# Analog_Section.net
KiCad netlist of a schematic drawn in Altium Designer
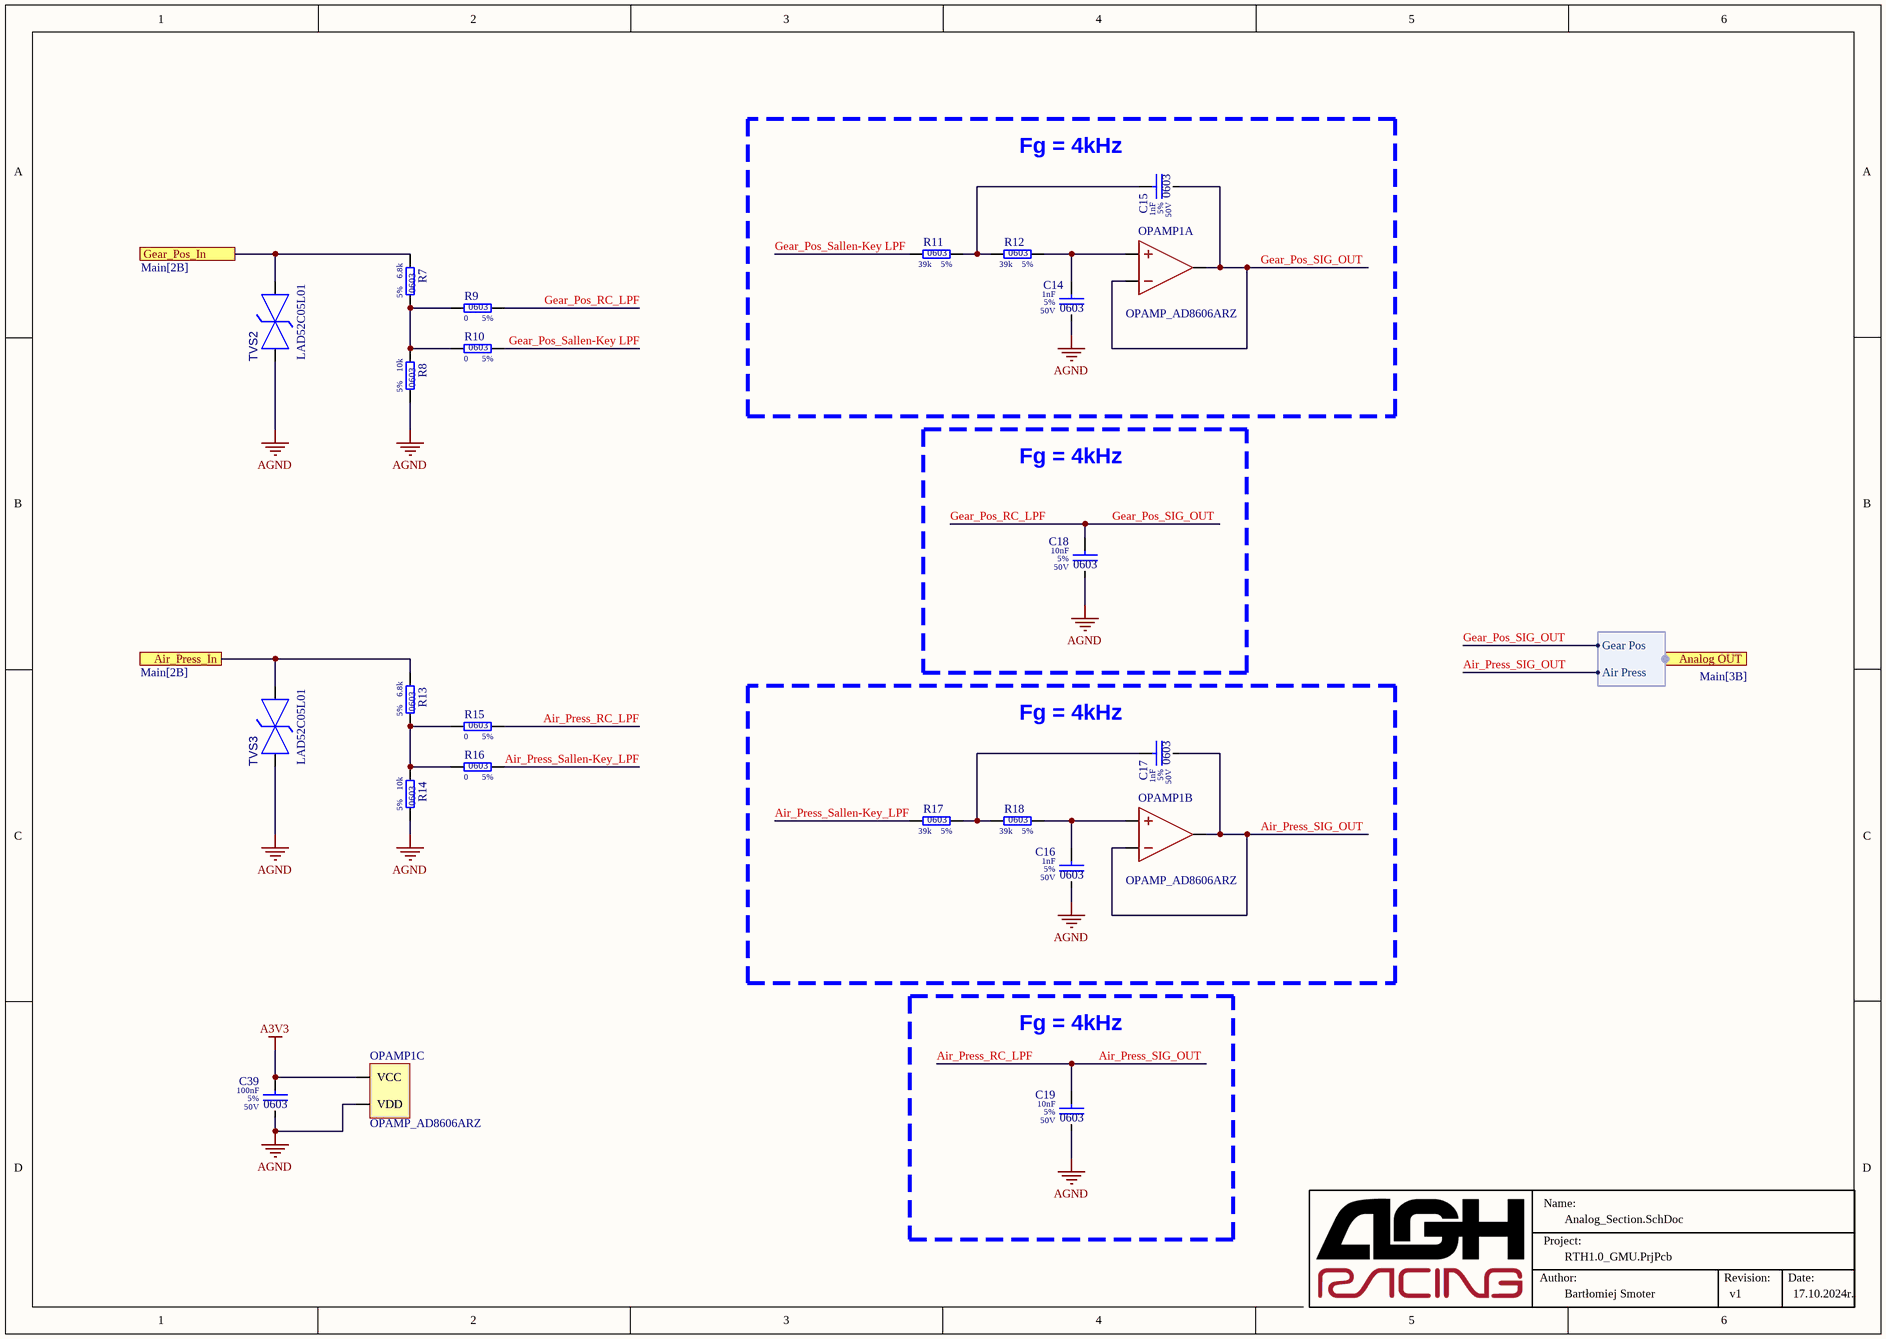
[diagram p0: Analog_Section.SchDoc]

(export (version "E")
  (design (tool "Eeschema 10.0.6"))
  (components
    (comp (ref "C14")
      (value "1nF")
      (footprint "0603_HandSold_Capacitor")
      (description "C_1n_50V_0603_5")
      (fields
        (field (name "TOLERANCE") "5%")
        (field (name "VOLTAGE RATING") "50V")
        (field (name "CASE/PACKAGE") "0603")
      )
      (libsource (lib "Altium Concord Pro on A365") (part "Capacitor"))
    )
    (comp (ref "C15")
      (value "1nF")
      (footprint "0603_HandSold_Capacitor")
      (description "C_1n_50V_0603_5")
      (fields
        (field (name "TOLERANCE") "5%")
        (field (name "VOLTAGE RATING") "50V")
        (field (name "CASE/PACKAGE") "0603")
      )
      (libsource (lib "Altium Concord Pro on A365") (part "Capacitor"))
    )
    (comp (ref "C16")
      (value "1nF")
      (footprint "0603_HandSold_Capacitor")
      (description "C_1n_50V_0603_5")
      (fields
        (field (name "TOLERANCE") "5%")
        (field (name "VOLTAGE RATING") "50V")
        (field (name "CASE/PACKAGE") "0603")
      )
      (libsource (lib "Altium Concord Pro on A365") (part "Capacitor"))
    )
    (comp (ref "C17")
      (value "1nF")
      (footprint "0603_HandSold_Capacitor")
      (description "C_1n_50V_0603_5")
      (fields
        (field (name "TOLERANCE") "5%")
        (field (name "VOLTAGE RATING") "50V")
        (field (name "CASE/PACKAGE") "0603")
      )
      (libsource (lib "Altium Concord Pro on A365") (part "Capacitor"))
    )
    (comp (ref "C18")
      (value "10nF")
      (footprint "0603_HandSold_Capacitor")
      (description "C_10n_50V_0603_5")
      (fields
        (field (name "TOLERANCE") "5%")
        (field (name "VOLTAGE RATING") "50V")
        (field (name "CASE/PACKAGE") "0603")
      )
      (libsource (lib "Altium Concord Pro on A365") (part "Capacitor"))
    )
    (comp (ref "C19")
      (value "10nF")
      (footprint "0603_HandSold_Capacitor")
      (description "C_10n_50V_0603_5")
      (fields
        (field (name "TOLERANCE") "5%")
        (field (name "VOLTAGE RATING") "50V")
        (field (name "CASE/PACKAGE") "0603")
      )
      (libsource (lib "Altium Concord Pro on A365") (part "Capacitor"))
    )
    (comp (ref "C39")
      (value "100nF")
      (footprint "0603_HandSold_Capacitor")
      (description "C_100n_50V_0603_5")
      (fields
        (field (name "TOLERANCE") "5%")
        (field (name "VOLTAGE RATING") "50V")
        (field (name "CASE/PACKAGE") "0603")
      )
      (libsource (lib "Altium Concord Pro on A365") (part "Capacitor"))
    )
    (comp (ref "OPAMP1")
      (value "OPAMP_AD8606ARZ")
      (footprint "SOIC-8")
      (fields (field (name "POWER") "1.25W"))
      (libsource (lib "Altium Concord Pro on A365") (part "OPAMP 2 Channels"))
    )
    (comp (ref "R7")
      (value "R_6.8k_0603_5")
      (footprint "0603_HandSold_Resistor")
      (fields
        (field (name "TOLERANCE") "5%")
        (field (name "RESISTANCE") "6.8k")
        (field (name "CASE/PACKAGE") "0603")
        (field (name "POWER") "100mW")
      )
      (libsource (lib "Altium Concord Pro on A365") (part "Resistor"))
    )
    (comp (ref "R8")
      (value "R_10k_0603_5")
      (footprint "0603_HandSold_Resistor")
      (fields
        (field (name "TOLERANCE") "5%")
        (field (name "RESISTANCE") "10k")
        (field (name "CASE/PACKAGE") "0603")
        (field (name "POWER") "100mW")
      )
      (libsource (lib "Altium Concord Pro on A365") (part "Resistor"))
    )
    (comp (ref "R9")
      (value "R_0_0603_5")
      (footprint "0603_HandSold_Resistor")
      (fields
        (field (name "TOLERANCE") "5%")
        (field (name "RESISTANCE") "0")
        (field (name "CASE/PACKAGE") "0603")
        (field (name "POWER") "100mW")
      )
      (libsource (lib "Altium Concord Pro on A365") (part "Resistor"))
    )
    (comp (ref "R10")
      (value "R_0_0603_5")
      (footprint "0603_HandSold_Resistor")
      (fields
        (field (name "TOLERANCE") "5%")
        (field (name "RESISTANCE") "0")
        (field (name "CASE/PACKAGE") "0603")
        (field (name "POWER") "100mW")
      )
      (libsource (lib "Altium Concord Pro on A365") (part "Resistor"))
    )
    (comp (ref "R11")
      (value "R_39k_0603_5")
      (footprint "0603_HandSold_Resistor")
      (fields
        (field (name "TOLERANCE") "5%")
        (field (name "RESISTANCE") "39k")
        (field (name "CASE/PACKAGE") "0603")
        (field (name "POWER") "100mW")
      )
      (libsource (lib "Altium Concord Pro on A365") (part "Resistor"))
    )
    (comp (ref "R12")
      (value "R_39k_0603_5")
      (footprint "0603_HandSold_Resistor")
      (fields
        (field (name "TOLERANCE") "5%")
        (field (name "RESISTANCE") "39k")
        (field (name "CASE/PACKAGE") "0603")
        (field (name "POWER") "100mW")
      )
      (libsource (lib "Altium Concord Pro on A365") (part "Resistor"))
    )
    (comp (ref "R13")
      (value "R_6.8k_0603_5")
      (footprint "0603_HandSold_Resistor")
      (fields
        (field (name "TOLERANCE") "5%")
        (field (name "RESISTANCE") "6.8k")
        (field (name "CASE/PACKAGE") "0603")
        (field (name "POWER") "100mW")
      )
      (libsource (lib "Altium Concord Pro on A365") (part "Resistor"))
    )
    (comp (ref "R14")
      (value "R_10k_0603_5")
      (footprint "0603_HandSold_Resistor")
      (fields
        (field (name "TOLERANCE") "5%")
        (field (name "RESISTANCE") "10k")
        (field (name "CASE/PACKAGE") "0603")
        (field (name "POWER") "100mW")
      )
      (libsource (lib "Altium Concord Pro on A365") (part "Resistor"))
    )
    (comp (ref "R15")
      (value "R_0_0603_5")
      (footprint "0603_HandSold_Resistor")
      (fields
        (field (name "TOLERANCE") "5%")
        (field (name "RESISTANCE") "0")
        (field (name "CASE/PACKAGE") "0603")
        (field (name "POWER") "100mW")
      )
      (libsource (lib "Altium Concord Pro on A365") (part "Resistor"))
    )
    (comp (ref "R16")
      (value "R_0_0603_5")
      (footprint "0603_HandSold_Resistor")
      (fields
        (field (name "TOLERANCE") "5%")
        (field (name "RESISTANCE") "0")
        (field (name "CASE/PACKAGE") "0603")
        (field (name "POWER") "100mW")
      )
      (libsource (lib "Altium Concord Pro on A365") (part "Resistor"))
    )
    (comp (ref "R17")
      (value "R_39k_0603_5")
      (footprint "0603_HandSold_Resistor")
      (fields
        (field (name "TOLERANCE") "5%")
        (field (name "RESISTANCE") "39k")
        (field (name "CASE/PACKAGE") "0603")
        (field (name "POWER") "100mW")
      )
      (libsource (lib "Altium Concord Pro on A365") (part "Resistor"))
    )
    (comp (ref "R18")
      (value "R_39k_0603_5")
      (footprint "0603_HandSold_Resistor")
      (fields
        (field (name "TOLERANCE") "5%")
        (field (name "RESISTANCE") "39k")
        (field (name "CASE/PACKAGE") "0603")
        (field (name "POWER") "100mW")
      )
      (libsource (lib "Altium Concord Pro on A365") (part "Resistor"))
    )
    (comp (ref "TVS2")
      (value "TVS_LAD52C05L01")
      (footprint "SOD-523-2_ALT")
      (description "Diode; TVS; 5V 5.6V 9.8V")
      (fields (field (name "MAN. PART NUM.") "LAD52C05L01"))
      (libsource (lib "Altium Concord Pro on A365") (part "TVS Bidirectional"))
    )
    (comp (ref "TVS3")
      (value "TVS_LAD52C05L01")
      (footprint "SOD-523-2_ALT")
      (description "Diode; TVS; 5V 5.6V 9.8V")
      (fields (field (name "MAN. PART NUM.") "LAD52C05L01"))
      (libsource (lib "Altium Concord Pro on A365") (part "TVS Bidirectional"))
    )
  )
  (nets
    (net (code "2") (name "/Air_Press_In") (class "Default")
      (node (ref "R13") (pin "1") (pinfunction "1_1") (pintype "passive"))
      (node (ref "TVS3") (pin "2") (pinfunction "2_2") (pintype "passive"))
    )
    (net (code "3") (name "/Air_Press_RC_LPF") (class "Default")
      (node (ref "C17") (pin "2") (pinfunction "2_2") (pintype "passive"))
      (node (ref "C19") (pin "1") (pinfunction "1_1") (pintype "passive"))
      (node (ref "OPAMP1") (pin "6") (pinfunction "2IN-_6") (pintype "passive"))
      (node (ref "OPAMP1") (pin "7") (pinfunction "2OUT_7") (pintype "passive"))
      (node (ref "R15") (pin "2") (pinfunction "2_2") (pintype "passive"))
    )
    (net (code "4") (name "/Air_Press_Sallen-Key_LPF") (class "Default")
      (node (ref "R16") (pin "2") (pinfunction "2_2") (pintype "passive"))
      (node (ref "R17") (pin "1") (pinfunction "1_1") (pintype "passive"))
    )
    (net (code "5") (name "/Gear_Pos_In") (class "Default")
      (node (ref "R7") (pin "1") (pinfunction "1_1") (pintype "passive"))
      (node (ref "TVS2") (pin "2") (pinfunction "2_2") (pintype "passive"))
    )
    (net (code "6") (name "/Gear_Pos_RC_LPF") (class "Default")
      (node (ref "C15") (pin "2") (pinfunction "2_2") (pintype "passive"))
      (node (ref "C18") (pin "1") (pinfunction "1_1") (pintype "passive"))
      (node (ref "OPAMP1") (pin "1") (pinfunction "1OUT_1") (pintype "passive"))
      (node (ref "OPAMP1") (pin "2") (pinfunction "1IN-_2") (pintype "passive"))
      (node (ref "R9") (pin "2") (pinfunction "2_2") (pintype "passive"))
    )
    (net (code "7") (name "/Gear_Pos_Sallen-Key LPF") (class "Default")
      (node (ref "R10") (pin "2") (pinfunction "2_2") (pintype "passive"))
      (node (ref "R11") (pin "1") (pinfunction "1_1") (pintype "passive"))
    )
    (net (code "9") (name "A3V3") (class "Default")
      (node (ref "C39") (pin "1") (pinfunction "1_1") (pintype "passive"))
      (node (ref "OPAMP1") (pin "8") (pinfunction "VCC_8") (pintype "passive"))
    )
    (net (code "10") (name "AGND") (class "Default")
      (node (ref "C14") (pin "2") (pinfunction "2_2") (pintype "passive"))
      (node (ref "C16") (pin "2") (pinfunction "2_2") (pintype "passive"))
      (node (ref "C18") (pin "2") (pinfunction "2_2") (pintype "passive"))
      (node (ref "C19") (pin "2") (pinfunction "2_2") (pintype "passive"))
      (node (ref "C39") (pin "2") (pinfunction "2_2") (pintype "passive"))
      (node (ref "OPAMP1") (pin "4") (pinfunction "VDD_4") (pintype "passive"))
      (node (ref "R14") (pin "2") (pinfunction "2_2") (pintype "passive"))
      (node (ref "R8") (pin "2") (pinfunction "2_2") (pintype "passive"))
      (node (ref "TVS2") (pin "1") (pinfunction "1_1") (pintype "passive"))
      (node (ref "TVS3") (pin "1") (pinfunction "1_1") (pintype "passive"))
    )
    (net (code "11") (name "Net-(C15-Pad1)") (class "Default")
      (node (ref "C15") (pin "1") (pinfunction "1_1") (pintype "passive"))
      (node (ref "R11") (pin "2") (pinfunction "2_2") (pintype "passive"))
      (node (ref "R12") (pin "1") (pinfunction "1_1") (pintype "passive"))
    )
    (net (code "12") (name "Net-(C17-Pad1)") (class "Default")
      (node (ref "C17") (pin "1") (pinfunction "1_1") (pintype "passive"))
      (node (ref "R17") (pin "2") (pinfunction "2_2") (pintype "passive"))
      (node (ref "R18") (pin "1") (pinfunction "1_1") (pintype "passive"))
    )
    (net (code "13") (name "Net-(OPAMP1A-1IN+)") (class "Default")
      (node (ref "C14") (pin "1") (pinfunction "1_1") (pintype "passive"))
      (node (ref "OPAMP1") (pin "3") (pinfunction "1IN+_3") (pintype "passive"))
      (node (ref "R12") (pin "2") (pinfunction "2_2") (pintype "passive"))
    )
    (net (code "14") (name "Net-(OPAMP1B-2IN+)") (class "Default")
      (node (ref "C16") (pin "1") (pinfunction "1_1") (pintype "passive"))
      (node (ref "OPAMP1") (pin "5") (pinfunction "2IN+_5") (pintype "passive"))
      (node (ref "R18") (pin "2") (pinfunction "2_2") (pintype "passive"))
    )
    (net (code "15") (name "Net-(R10-Pad1)") (class "Default")
      (node (ref "R10") (pin "1") (pinfunction "1_1") (pintype "passive"))
      (node (ref "R7") (pin "2") (pinfunction "2_2") (pintype "passive"))
      (node (ref "R8") (pin "1") (pinfunction "1_1") (pintype "passive"))
      (node (ref "R9") (pin "1") (pinfunction "1_1") (pintype "passive"))
    )
    (net (code "16") (name "Net-(R13-Pad2)") (class "Default")
      (node (ref "R13") (pin "2") (pinfunction "2_2") (pintype "passive"))
      (node (ref "R14") (pin "1") (pinfunction "1_1") (pintype "passive"))
      (node (ref "R15") (pin "1") (pinfunction "1_1") (pintype "passive"))
      (node (ref "R16") (pin "1") (pinfunction "1_1") (pintype "passive"))
    )
  )
)
